# Example.net
KiCad netlist of a schematic drawn in EAGLE
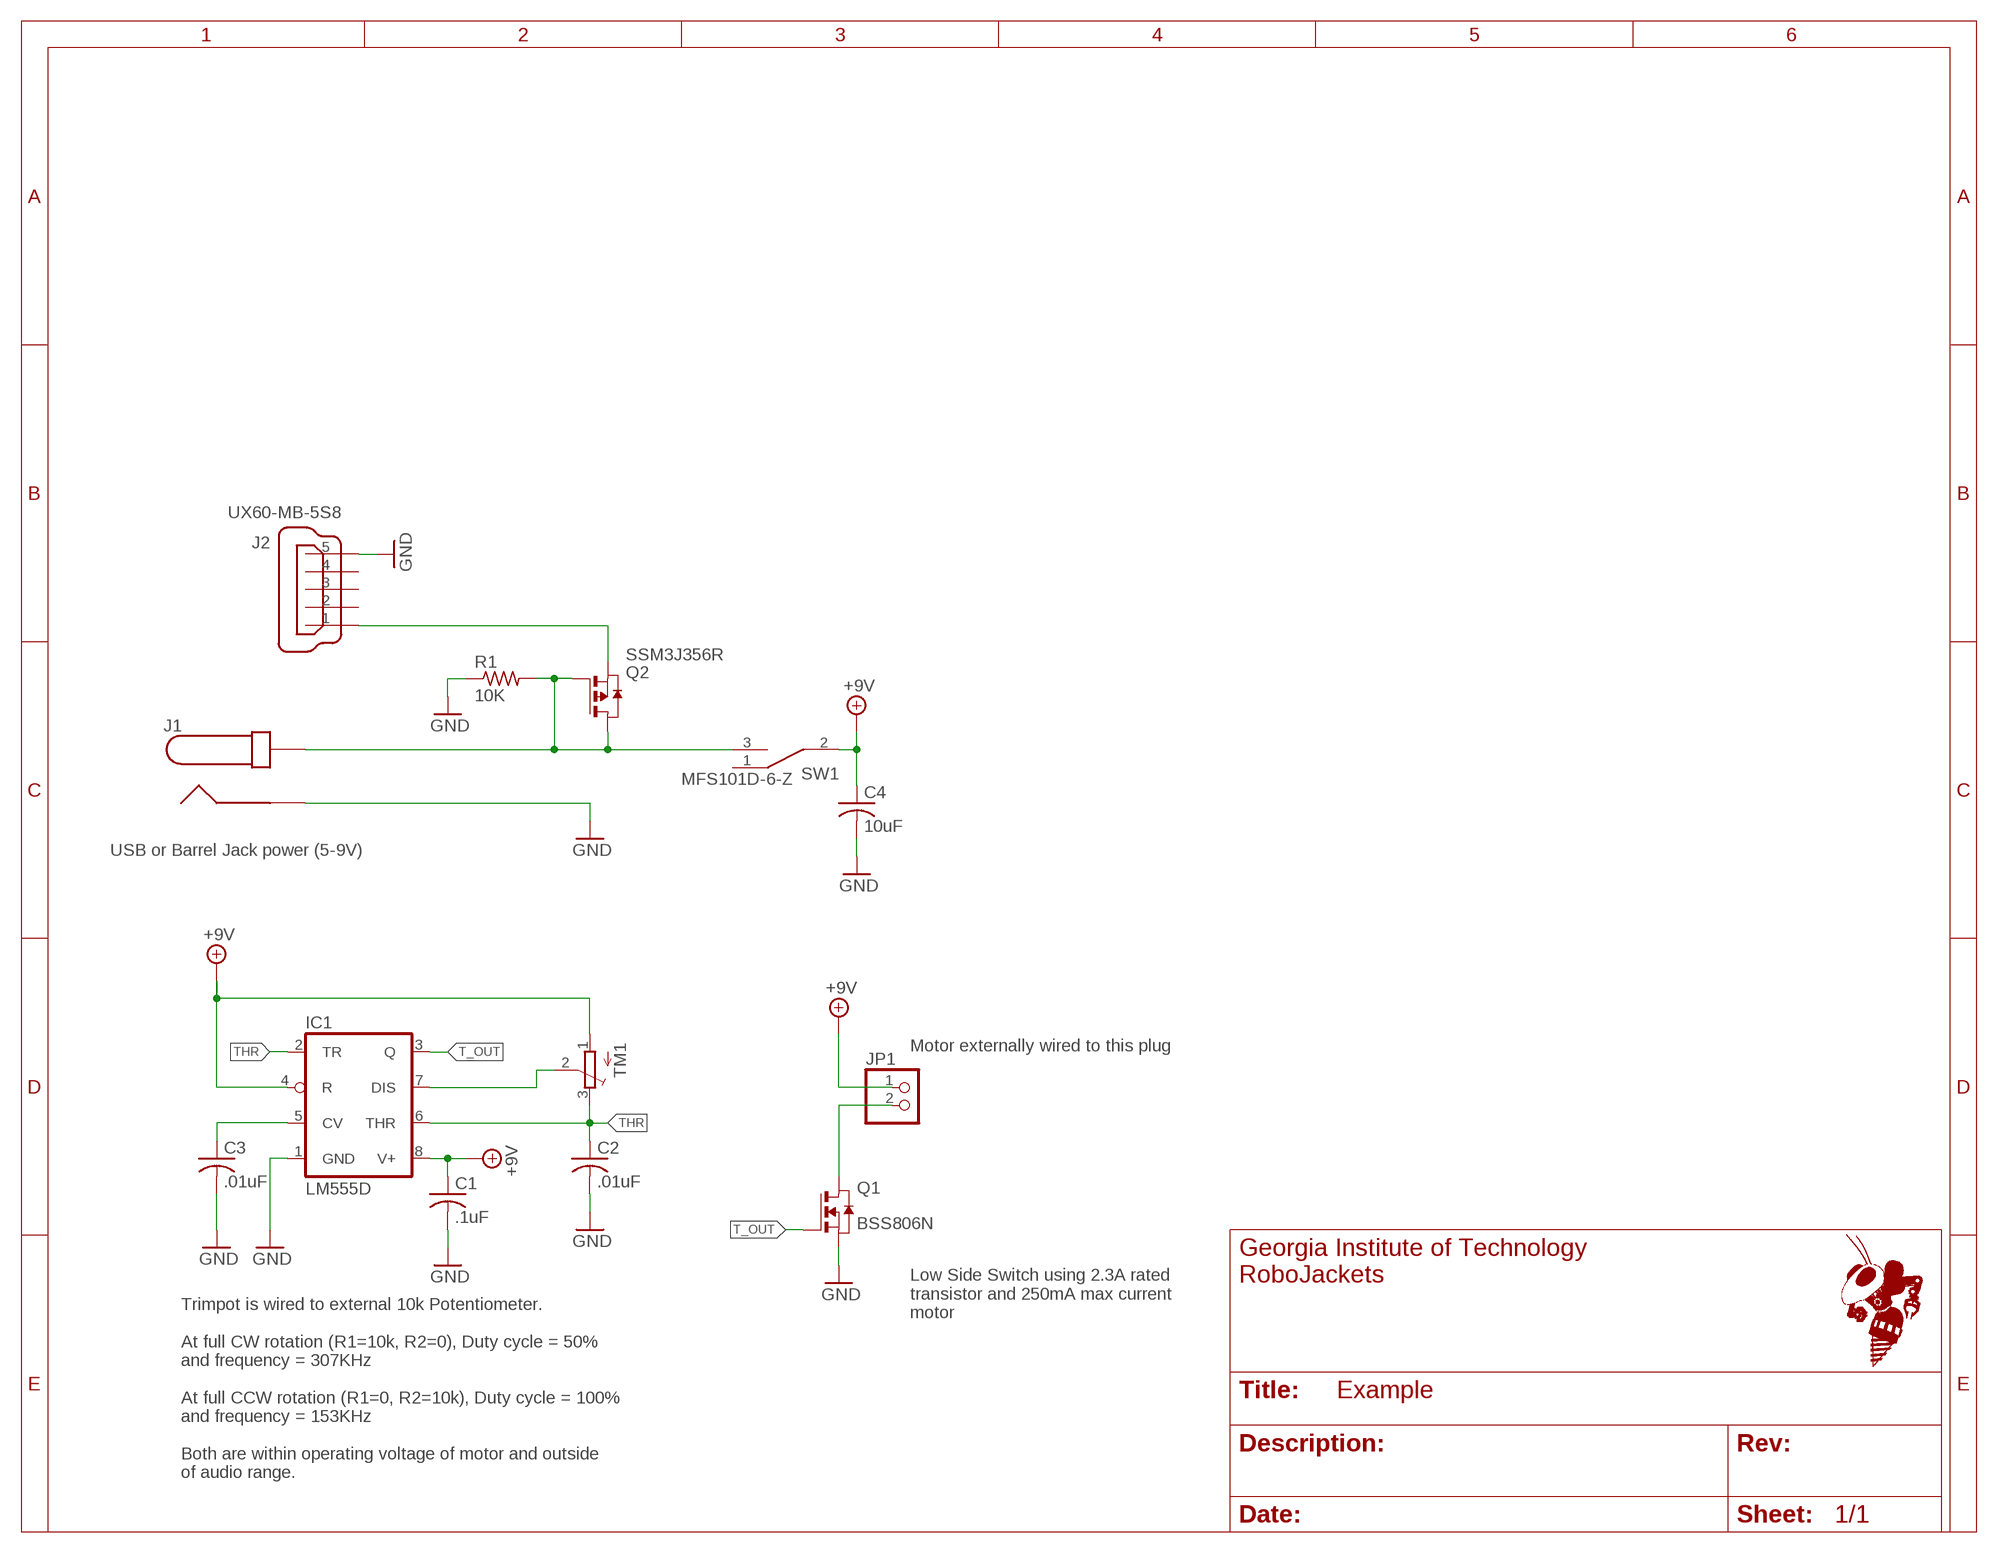
[diagram p0: schematic, sheet 1]

(export (version "E")
  (design (tool "Eeschema 10.0.6"))
  (components
    (comp (ref "C1")
      (value ".1uF")
      (footprint "eagle-import:C0603")
      (libsource (lib "eagle-import") (part "C-USC0603"))
    )
    (comp (ref "C2")
      (value ".01uF")
      (footprint "eagle-import:C0603")
      (libsource (lib "eagle-import") (part "C-USC0603"))
    )
    (comp (ref "C3")
      (value ".01uF")
      (footprint "eagle-import:C0603")
      (libsource (lib "eagle-import") (part "C-USC0603"))
    )
    (comp (ref "C4")
      (value "10uF")
      (footprint "eagle-import:C0603")
      (libsource (lib "eagle-import") (part "C-USC0603"))
    )
    (comp (ref "IC1")
      (value "LM555D")
      (footprint "eagle-import:SO08")
      (libsource (lib "eagle-import") (part "555DLM"))
    )
    (comp (ref "J1")
      (value "PJ-037A")
      (footprint "eagle-import:PJ-037A")
      (libsource (lib "eagle-import") (part "PJ-037A"))
    )
    (comp (ref "J2")
      (value "UX60-MB-5S8")
      (footprint "eagle-import:UX60-MB-5S8")
      (libsource (lib "eagle-import") (part "UX60-MB-5S?8"))
    )
    (comp (ref "JP1")
      (value "PINHD-1X2")
      (footprint "eagle-import:1X02")
      (libsource (lib "eagle-import") (part "PINHD-1X2"))
    )
    (comp (ref "Q1")
      (value "BSS806N")
      (footprint "eagle-import:SOT-23-3")
      (libsource (lib "eagle-import") (part "BSS806N"))
    )
    (comp (ref "Q2")
      (value "SSM3J356R")
      (footprint "eagle-import:SOT95P240X80-3N")
      (libsource (lib "eagle-import") (part "SSM3J356R"))
    )
    (comp (ref "R1")
      (value "10K")
      (footprint "eagle-import:R0603")
      (libsource (lib "eagle-import") (part "R-US_R0603"))
    )
    (comp (ref "SW1")
      (value "MFS101D-6-Z")
      (footprint "eagle-import:MFS101D-6-Z")
      (libsource (lib "eagle-import") (part "MFS101D-6-Z"))
    )
    (comp (ref "TM1")
      (value "TRIMPOT3386")
      (footprint "eagle-import:TRIM-3386")
      (libsource (lib "eagle-import") (part "TRIMPOT3386"))
    )
  )
  (nets
    (net (code "1") (name "+9V") (class "Default")
      (node (ref "C1") (pin "1") (pinfunction "1_1") (pintype "passive"))
      (node (ref "C4") (pin "1") (pinfunction "1_1") (pintype "passive"))
      (node (ref "IC1") (pin "4") (pinfunction "R_4") (pintype "input"))
      (node (ref "IC1") (pin "8") (pinfunction "V+_8") (pintype "power_in"))
      (node (ref "JP1") (pin "1") (pinfunction "1_1") (pintype "passive"))
      (node (ref "SW1") (pin "2") (pinfunction "COMMON_2") (pintype "bidirectional"))
      (node (ref "TM1") (pin "1") (pinfunction "A_1") (pintype "passive"))
    )
    (net (code "2") (name "GND") (class "Default")
      (node (ref "C1") (pin "2") (pinfunction "2_2") (pintype "passive"))
      (node (ref "C2") (pin "2") (pinfunction "2_2") (pintype "passive"))
      (node (ref "C3") (pin "2") (pinfunction "2_2") (pintype "passive"))
      (node (ref "C4") (pin "2") (pinfunction "2_2") (pintype "passive"))
      (node (ref "IC1") (pin "1") (pinfunction "GND_1") (pintype "power_in"))
      (node (ref "J1") (pin "P$1") (pinfunction "2_P$1") (pintype "bidirectional"))
      (node (ref "J2") (pin "5") (pinfunction "5_5") (pintype "passive"))
      (node (ref "Q1") (pin "2") (pinfunction "S_2") (pintype "passive"))
      (node (ref "R1") (pin "1") (pinfunction "1_1") (pintype "passive"))
    )
    (net (code "3") (name "Net-(IC1-CV)") (class "Default")
      (node (ref "C3") (pin "1") (pinfunction "1_1") (pintype "passive"))
      (node (ref "IC1") (pin "5") (pinfunction "CV_5") (pintype "input"))
    )
    (net (code "4") (name "Net-(IC1-DIS)") (class "Default")
      (node (ref "IC1") (pin "7") (pinfunction "DIS_7") (pintype "input"))
      (node (ref "TM1") (pin "2") (pinfunction "S_2") (pintype "passive"))
    )
    (net (code "5") (name "Net-(J1-1)") (class "Default")
      (node (ref "J1") (pin "P$2") (pinfunction "1_P$2") (pintype "bidirectional"))
      (node (ref "Q2") (pin "1") (pinfunction "G_1") (pintype "passive"))
      (node (ref "Q2") (pin "2") (pinfunction "D_2") (pintype "passive"))
      (node (ref "R1") (pin "2") (pinfunction "2_2") (pintype "passive"))
      (node (ref "SW1") (pin "3") (pinfunction "B_3") (pintype "bidirectional"))
    )
    (net (code "6") (name "Net-(Q1-D)") (class "Default")
      (node (ref "JP1") (pin "2") (pinfunction "2_2") (pintype "passive"))
      (node (ref "Q1") (pin "3") (pinfunction "D_3") (pintype "passive"))
    )
    (net (code "7") (name "Net-(Q2-S)") (class "Default")
      (node (ref "J2") (pin "1") (pinfunction "1_1") (pintype "passive"))
      (node (ref "Q2") (pin "3") (pinfunction "S_3") (pintype "passive"))
    )
    (net (code "8") (name "THR") (class "Default")
      (node (ref "C2") (pin "1") (pinfunction "1_1") (pintype "passive"))
      (node (ref "IC1") (pin "2") (pinfunction "TR_2") (pintype "input"))
      (node (ref "IC1") (pin "6") (pinfunction "THR_6") (pintype "input"))
      (node (ref "TM1") (pin "3") (pinfunction "E_3") (pintype "passive"))
    )
    (net (code "9") (name "T_OUT") (class "Default")
      (node (ref "IC1") (pin "3") (pinfunction "Q_3") (pintype "output"))
      (node (ref "Q1") (pin "1") (pinfunction "G_1") (pintype "passive"))
    )
    (net (code "10") (name "unconnected-(J2-Pad2)") (class "Default")
      (node (ref "J2") (pin "2") (pinfunction "2_2") (pintype "passive"))
    )
    (net (code "11") (name "unconnected-(J2-Pad3)") (class "Default")
      (node (ref "J2") (pin "3") (pinfunction "3_3") (pintype "passive"))
    )
    (net (code "12") (name "unconnected-(J2-Pad4)") (class "Default")
      (node (ref "J2") (pin "4") (pinfunction "4_4") (pintype "passive"))
    )
    (net (code "13") (name "unconnected-(SW1-A-Pad1)") (class "Default")
      (node (ref "SW1") (pin "1") (pinfunction "A_1") (pintype "bidirectional"))
    )
  )
)
